# motor_drive_basic.net
KiCad netlist of a schematic drawn in EAGLE
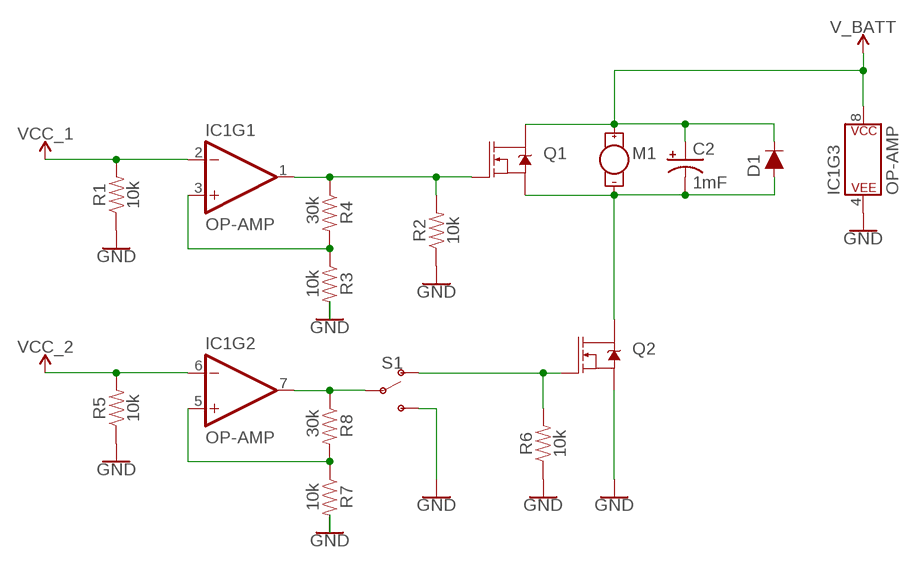
[diagram p0: schematic, sheet 1]

(export (version "E")
  (design (tool "Eeschema 10.0.6"))
  (components
    (comp (ref "C2")
      (value "1mF")
      (footprint "eagle-import:CPOL-RADIAL-5MM-10MM")
      (libsource (lib "eagle-import") (part "1000UF-RADIAL-5MM-25V-20%"))
    )
    (comp (ref "D1")
      (value "DIODE-1N4148")
      (footprint "eagle-import:DIODE-1N4148")
      (libsource (lib "eagle-import") (part "DIODE-1N4148"))
    )
    (comp (ref "IC1")
      (value "OP-AMP")
      (footprint "eagle-import:DIP08")
      (libsource (lib "eagle-import") (part "OPAMP-DUALDIP"))
    )
    (comp (ref "M1")
      (value "MOTOR10MM")
      (footprint "eagle-import:VIBE-MOTOR-10MM")
      (libsource (lib "eagle-import") (part "MOTOR10MM"))
    )
    (comp (ref "Q1")
      (value "MOSFET-NCH-FQP30N06L")
      (footprint "eagle-import:TO220V")
      (libsource (lib "eagle-import") (part "MOSFET-NCH-FQP30N06L"))
    )
    (comp (ref "Q2")
      (value "MOSFET-NCH-FQP30N06L")
      (footprint "eagle-import:TO220V")
      (libsource (lib "eagle-import") (part "MOSFET-NCH-FQP30N06L"))
    )
    (comp (ref "R1")
      (value "10k")
      (footprint "eagle-import:AXIAL-0.3")
      (libsource (lib "eagle-import") (part "10KOHM-HORIZ-1/4W-1%"))
    )
    (comp (ref "R2")
      (value "10k")
      (footprint "eagle-import:AXIAL-0.3")
      (libsource (lib "eagle-import") (part "10KOHM-HORIZ-1/4W-1%"))
    )
    (comp (ref "R3")
      (value "10k")
      (footprint "eagle-import:AXIAL-0.3")
      (libsource (lib "eagle-import") (part "10KOHM-HORIZ-1/4W-1%"))
    )
    (comp (ref "R4")
      (value "30k")
      (footprint "eagle-import:AXIAL-0.3")
      (libsource (lib "eagle-import") (part "RESISTORAXIAL-0.3"))
    )
    (comp (ref "R5")
      (value "10k")
      (footprint "eagle-import:AXIAL-0.3")
      (libsource (lib "eagle-import") (part "10KOHM-HORIZ-1/4W-1%"))
    )
    (comp (ref "R6")
      (value "10k")
      (footprint "eagle-import:AXIAL-0.3")
      (libsource (lib "eagle-import") (part "10KOHM-HORIZ-1/4W-1%"))
    )
    (comp (ref "R7")
      (value "10k")
      (footprint "eagle-import:AXIAL-0.3")
      (libsource (lib "eagle-import") (part "10KOHM-HORIZ-1/4W-1%"))
    )
    (comp (ref "R8")
      (value "30k")
      (footprint "eagle-import:AXIAL-0.3")
      (libsource (lib "eagle-import") (part "RESISTORAXIAL-0.3"))
    )
    (comp (ref "S1")
      (value "SWITCH-SPDT-PTH-11.6X4.0MM-KIT")
      (footprint "eagle-import:SWITCH_SPDT_PTH_11.6X4.0MM_KIT")
      (libsource (lib "eagle-import") (part "SWITCH-SPDT-PTH-11.6X4.0MM-KIT"))
    )
  )
  (nets
    (net (code "1") (name "GND") (class "Default")
      (node (ref "IC1") (pin "4") (pinfunction "P$V-_4") (pintype "bidirectional"))
      (node (ref "Q2") (pin "3") (pinfunction "S_3") (pintype "bidirectional"))
      (node (ref "R1") (pin "P$1") (pinfunction "1_P$1") (pintype "passive"))
      (node (ref "R2") (pin "P$1") (pinfunction "1_P$1") (pintype "passive"))
      (node (ref "R3") (pin "P$2") (pinfunction "2_P$2") (pintype "passive"))
      (node (ref "R5") (pin "P$1") (pinfunction "1_P$1") (pintype "passive"))
      (node (ref "R6") (pin "P$1") (pinfunction "1_P$1") (pintype "passive"))
      (node (ref "R7") (pin "P$2") (pinfunction "2_P$2") (pintype "passive"))
      (node (ref "S1") (pin "3") (pinfunction "S_3") (pintype "passive"))
    )
    (net (code "2") (name "Net-(IC1A-+IN)") (class "Default")
      (node (ref "IC1") (pin "3") (pinfunction "+IN_3") (pintype "input"))
      (node (ref "R3") (pin "P$1") (pinfunction "1_P$1") (pintype "passive"))
      (node (ref "R4") (pin "P$2") (pinfunction "2_P$2") (pintype "passive"))
    )
    (net (code "3") (name "Net-(IC1A-OUT)") (class "Default")
      (node (ref "IC1") (pin "1") (pinfunction "OUT_1") (pintype "output"))
      (node (ref "Q1") (pin "1") (pinfunction "G_1") (pintype "bidirectional"))
      (node (ref "R2") (pin "P$2") (pinfunction "2_P$2") (pintype "passive"))
      (node (ref "R4") (pin "P$1") (pinfunction "1_P$1") (pintype "passive"))
    )
    (net (code "4") (name "Net-(IC1B-+IN)") (class "Default")
      (node (ref "IC1") (pin "5") (pinfunction "+IN_5") (pintype "input"))
      (node (ref "R7") (pin "P$1") (pinfunction "1_P$1") (pintype "passive"))
      (node (ref "R8") (pin "P$2") (pinfunction "2_P$2") (pintype "passive"))
    )
    (net (code "5") (name "Net-(IC1B-OUT)") (class "Default")
      (node (ref "IC1") (pin "7") (pinfunction "OUT_7") (pintype "output"))
      (node (ref "R8") (pin "P$1") (pinfunction "1_P$1") (pintype "passive"))
      (node (ref "S1") (pin "2") (pinfunction "P_2") (pintype "passive"))
    )
    (net (code "6") (name "Net-(Q1-S)") (class "Default")
      (node (ref "C2") (pin "-") (pinfunction "-_-") (pintype "passive"))
      (node (ref "D1") (pin "A") (pinfunction "A_A") (pintype "passive"))
      (node (ref "M1") (pin "-") (pinfunction "-_-") (pintype "bidirectional"))
      (node (ref "Q1") (pin "3") (pinfunction "S_3") (pintype "bidirectional"))
      (node (ref "Q2") (pin "2") (pinfunction "D_2") (pintype "bidirectional"))
    )
    (net (code "7") (name "Net-(Q2-G)") (class "Default")
      (node (ref "Q2") (pin "1") (pinfunction "G_1") (pintype "bidirectional"))
      (node (ref "R6") (pin "P$2") (pinfunction "2_P$2") (pintype "passive"))
      (node (ref "S1") (pin "1") (pinfunction "O_1") (pintype "passive"))
    )
    (net (code "8") (name "VCC_1") (class "Default")
      (node (ref "IC1") (pin "2") (pinfunction "-IN_2") (pintype "input"))
      (node (ref "R1") (pin "P$2") (pinfunction "2_P$2") (pintype "passive"))
    )
    (net (code "9") (name "VCC_2") (class "Default")
      (node (ref "IC1") (pin "6") (pinfunction "-IN_6") (pintype "input"))
      (node (ref "R5") (pin "P$2") (pinfunction "2_P$2") (pintype "passive"))
    )
    (net (code "10") (name "V_BATT") (class "Default")
      (node (ref "C2") (pin "+") (pinfunction "+_+") (pintype "passive"))
      (node (ref "D1") (pin "C") (pinfunction "C_C") (pintype "passive"))
      (node (ref "IC1") (pin "8") (pinfunction "P$V+_8") (pintype "bidirectional"))
      (node (ref "M1") (pin "+") (pinfunction "+_+") (pintype "bidirectional"))
      (node (ref "Q1") (pin "2") (pinfunction "D_2") (pintype "bidirectional"))
    )
  )
)
